# sensors.net
KiCad netlist of a schematic drawn in Altium Designer
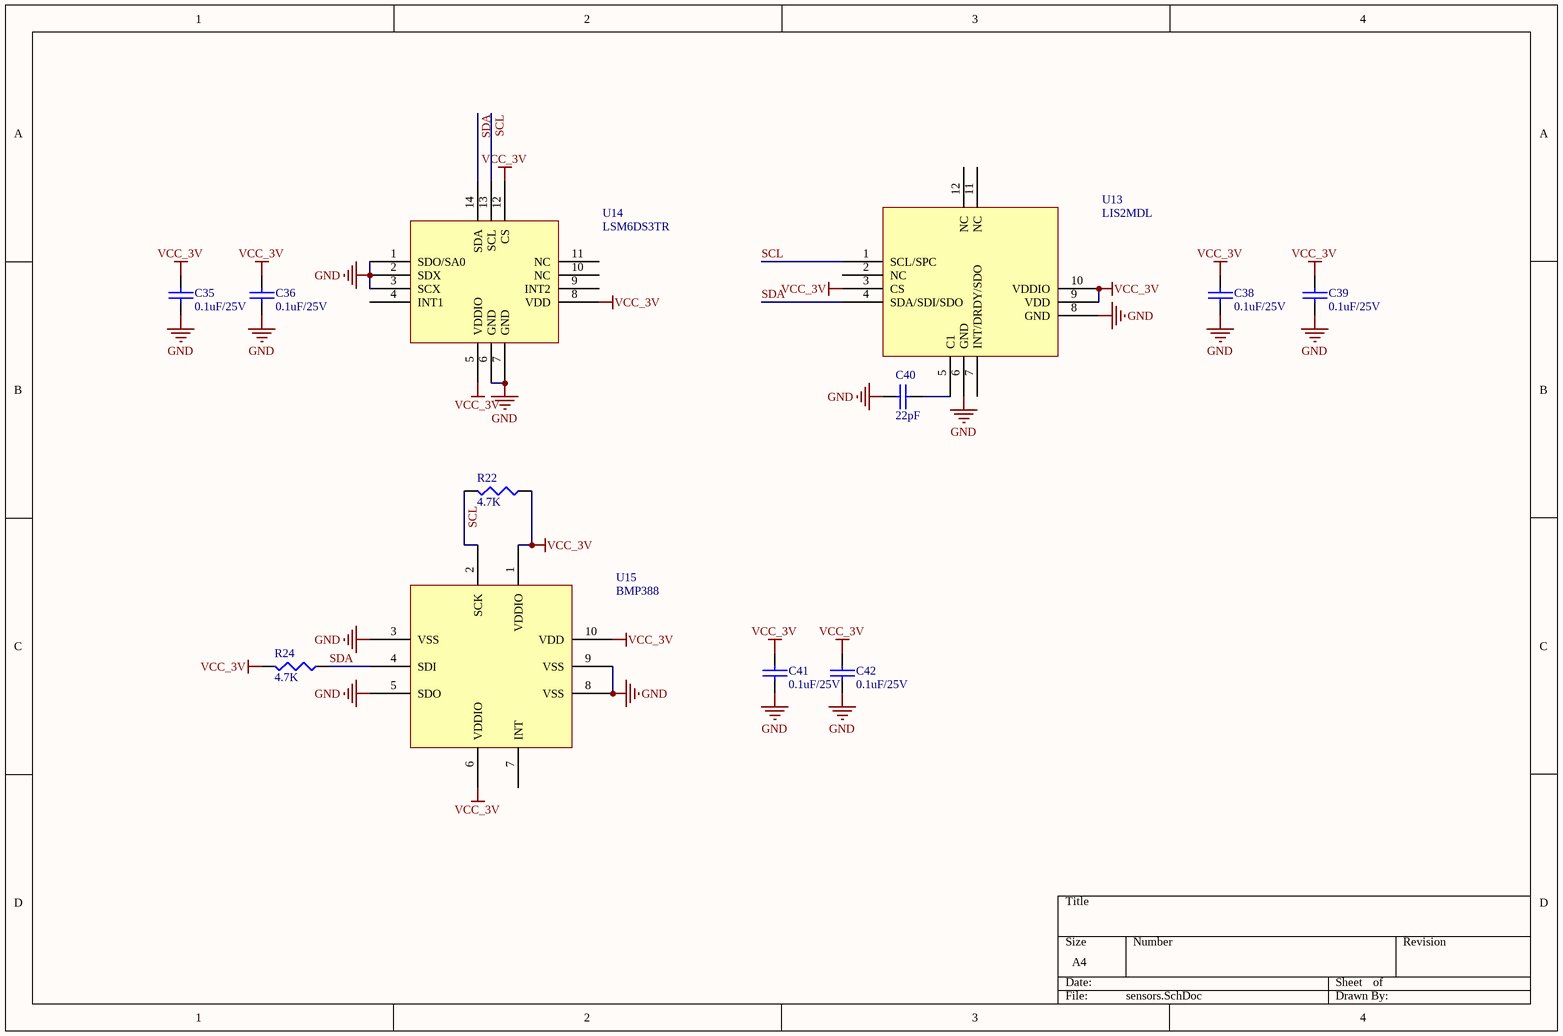
[diagram p0: sensors.SchDoc]

(export (version "E")
  (design (tool "Eeschema 10.0.6"))
  (components
    (comp (ref "C35")
      (value "0.1uF/25V")
      (footprint "0402C")
      (description "Capacitor")
      (libsource (lib "ZWLIntegrated_Library") (part "CAP"))
    )
    (comp (ref "C36")
      (value "0.1uF/25V")
      (footprint "0402C")
      (description "Capacitor")
      (libsource (lib "ZWLIntegrated_Library") (part "CAP"))
    )
    (comp (ref "C38")
      (value "0.1uF/25V")
      (footprint "0402C")
      (description "Capacitor")
      (libsource (lib "ZWLIntegrated_Library") (part "CAP"))
    )
    (comp (ref "C39")
      (value "0.1uF/25V")
      (footprint "0402C")
      (description "Capacitor")
      (libsource (lib "ZWLIntegrated_Library") (part "CAP"))
    )
    (comp (ref "C40")
      (value "22pF")
      (footprint "0402c")
      (description "Capacitor")
      (libsource (lib "SM") (part "CAP"))
    )
    (comp (ref "C41")
      (value "0.1uF/25V")
      (footprint "0402C")
      (description "Capacitor")
      (libsource (lib "ZWLIntegrated_Library") (part "CAP"))
    )
    (comp (ref "C42")
      (value "0.1uF/25V")
      (footprint "0402C")
      (description "Capacitor")
      (libsource (lib "ZWLIntegrated_Library") (part "CAP"))
    )
    (comp (ref "R22")
      (value "4.7K")
      (footprint "0402R")
      (libsource (lib "ZWLIntegrated_Library") (part "RES1"))
    )
    (comp (ref "R24")
      (value "4.7K")
      (footprint "0402R")
      (libsource (lib "ZWLIntegrated_Library") (part "RES1"))
    )
    (comp (ref "U13") (value "LIS2MDL") (footprint "LIS2MDL") (libsource (lib "stm32") (part "LIS2MDL")))
    (comp (ref "U14")
      (value "LSM6DS3TR")
      (footprint "LSM6DS3TR-C")
      (libsource (lib "stm32") (part "LSM6DS3TR"))
    )
    (comp (ref "U15") (value "BMP388") (footprint "BMP388") (libsource (lib "stm32") (part "BMP388")))
  )
  (nets
    (net (code "1") (name "/SCL") (class "Default")
      (node (ref "R22") (pin "2") (pinfunction "2_2") (pintype "passive"))
      (node (ref "U13") (pin "1") (pinfunction "SCL/SPC_1") (pintype "passive"))
      (node (ref "U14") (pin "13") (pinfunction "SCL_13") (pintype "passive"))
      (node (ref "U15") (pin "2") (pinfunction "SCK_2") (pintype "passive"))
    )
    (net (code "2") (name "/SDA") (class "Default")
      (node (ref "R24") (pin "1") (pinfunction "1_1") (pintype "passive"))
      (node (ref "U13") (pin "4") (pinfunction "SDA/SDI/SDO_4") (pintype "passive"))
      (node (ref "U14") (pin "14") (pinfunction "SDA_14") (pintype "passive"))
      (node (ref "U15") (pin "4") (pinfunction "SDI_4") (pintype "passive"))
    )
    (net (code "3") (name "GND") (class "Default")
      (node (ref "C35") (pin "1") (pinfunction "1_1") (pintype "passive"))
      (node (ref "C36") (pin "1") (pinfunction "1_1") (pintype "passive"))
      (node (ref "C38") (pin "1") (pinfunction "1_1") (pintype "passive"))
      (node (ref "C39") (pin "1") (pinfunction "1_1") (pintype "passive"))
      (node (ref "C40") (pin "2") (pinfunction "2_2") (pintype "passive"))
      (node (ref "C41") (pin "1") (pinfunction "1_1") (pintype "passive"))
      (node (ref "C42") (pin "1") (pinfunction "1_1") (pintype "passive"))
      (node (ref "U13") (pin "6") (pinfunction "GND_6") (pintype "passive"))
      (node (ref "U13") (pin "8") (pinfunction "GND_8") (pintype "passive"))
      (node (ref "U14") (pin "1") (pinfunction "SDO/SA0_1") (pintype "passive"))
      (node (ref "U14") (pin "2") (pinfunction "SDX_2") (pintype "passive"))
      (node (ref "U14") (pin "3") (pinfunction "SCX_3") (pintype "passive"))
      (node (ref "U14") (pin "6") (pinfunction "GND_6") (pintype "passive"))
      (node (ref "U14") (pin "7") (pinfunction "GND_7") (pintype "passive"))
      (node (ref "U15") (pin "3") (pinfunction "VSS_3") (pintype "passive"))
      (node (ref "U15") (pin "5") (pinfunction "SDO_5") (pintype "passive"))
      (node (ref "U15") (pin "8") (pinfunction "VSS_8") (pintype "passive"))
      (node (ref "U15") (pin "9") (pinfunction "VSS_9") (pintype "passive"))
    )
    (net (code "4") (name "Net-(U13-C1)") (class "Default")
      (node (ref "C40") (pin "1") (pinfunction "1_1") (pintype "passive"))
      (node (ref "U13") (pin "5") (pinfunction "C1_5") (pintype "passive"))
    )
    (net (code "5") (name "VCC_3V") (class "Default")
      (node (ref "C35") (pin "2") (pinfunction "2_2") (pintype "passive"))
      (node (ref "C36") (pin "2") (pinfunction "2_2") (pintype "passive"))
      (node (ref "C38") (pin "2") (pinfunction "2_2") (pintype "passive"))
      (node (ref "C39") (pin "2") (pinfunction "2_2") (pintype "passive"))
      (node (ref "C41") (pin "2") (pinfunction "2_2") (pintype "passive"))
      (node (ref "C42") (pin "2") (pinfunction "2_2") (pintype "passive"))
      (node (ref "R22") (pin "1") (pinfunction "1_1") (pintype "passive"))
      (node (ref "R24") (pin "2") (pinfunction "2_2") (pintype "passive"))
      (node (ref "U13") (pin "10") (pinfunction "VDDIO_10") (pintype "passive"))
      (node (ref "U13") (pin "3") (pinfunction "CS_3") (pintype "passive"))
      (node (ref "U13") (pin "9") (pinfunction "VDD_9") (pintype "passive"))
      (node (ref "U14") (pin "12") (pinfunction "CS_12") (pintype "passive"))
      (node (ref "U14") (pin "5") (pinfunction "VDDIO_5") (pintype "passive"))
      (node (ref "U14") (pin "8") (pinfunction "VDD_8") (pintype "passive"))
      (node (ref "U15") (pin "1") (pinfunction "VDDIO_1") (pintype "passive"))
      (node (ref "U15") (pin "10") (pinfunction "VDD_10") (pintype "passive"))
      (node (ref "U15") (pin "6") (pinfunction "VDDIO_6") (pintype "passive"))
    )
    (net (code "6") (name "unconnected-(U13-INT{slash}DRDY{slash}SDO-Pad7)") (class "Default")
      (node (ref "U13") (pin "7") (pinfunction "INT/DRDY/SDO_7") (pintype "passive"))
    )
    (net (code "7") (name "unconnected-(U13-NC-Pad2)") (class "Default")
      (node (ref "U13") (pin "2") (pinfunction "NC_2") (pintype "passive"))
    )
    (net (code "8") (name "unconnected-(U13-NC-Pad11)") (class "Default")
      (node (ref "U13") (pin "11") (pinfunction "NC_11") (pintype "passive"))
    )
    (net (code "9") (name "unconnected-(U13-NC-Pad12)") (class "Default")
      (node (ref "U13") (pin "12") (pinfunction "NC_12") (pintype "passive"))
    )
    (net (code "10") (name "unconnected-(U14-INT1-Pad4)") (class "Default")
      (node (ref "U14") (pin "4") (pinfunction "INT1_4") (pintype "passive"))
    )
    (net (code "11") (name "unconnected-(U14-INT2-Pad9)") (class "Default")
      (node (ref "U14") (pin "9") (pinfunction "INT2_9") (pintype "passive"))
    )
    (net (code "12") (name "unconnected-(U14-NC-Pad10)") (class "Default")
      (node (ref "U14") (pin "10") (pinfunction "NC_10") (pintype "passive"))
    )
    (net (code "13") (name "unconnected-(U14-NC-Pad11)") (class "Default")
      (node (ref "U14") (pin "11") (pinfunction "NC_11") (pintype "passive"))
    )
    (net (code "14") (name "unconnected-(U15-INT-Pad7)") (class "Default")
      (node (ref "U15") (pin "7") (pinfunction "INT_7") (pintype "passive"))
    )
  )
)
